# piezo-preamp-tickler_V1-01a.net
KiCad netlist of a schematic drawn in EAGLE
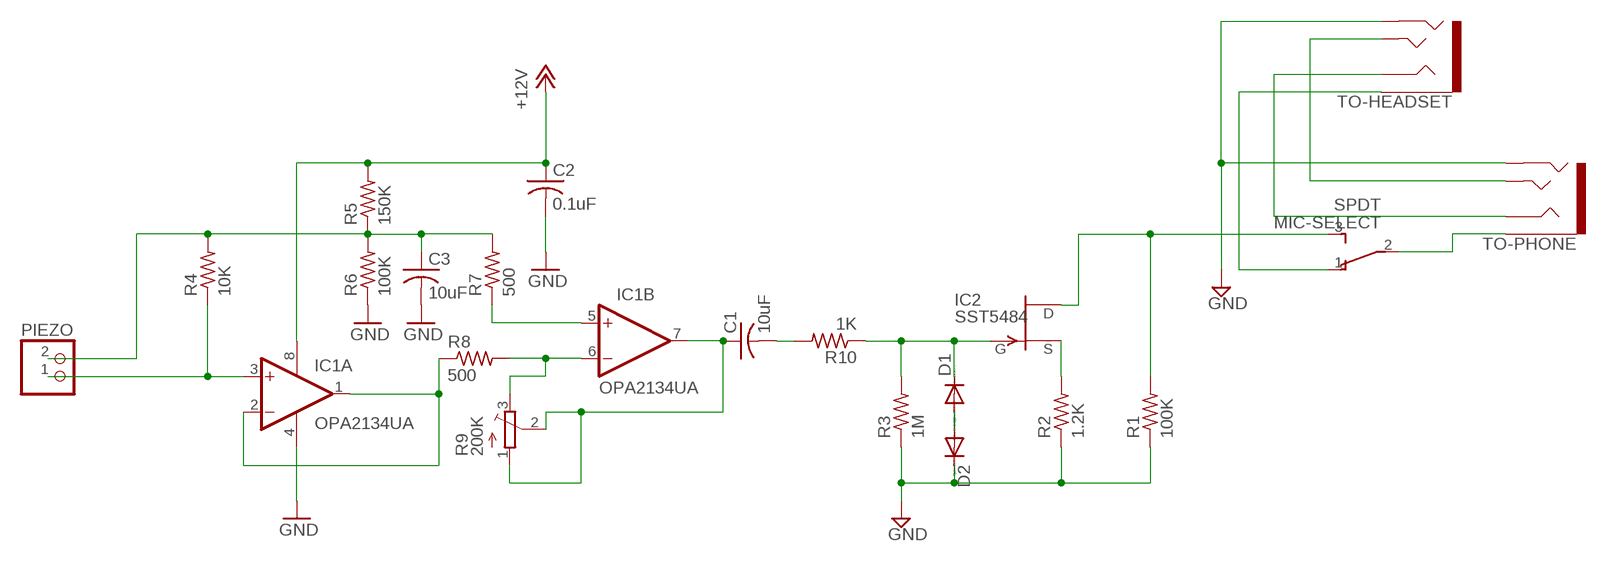
[diagram p0: schematic, sheet 1]
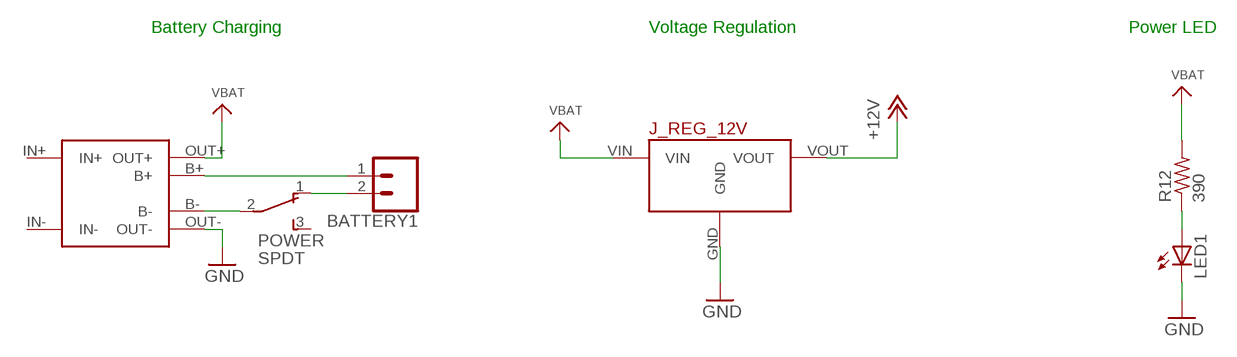
[diagram p1: schematic, sheet 2]

(export (version "E")
  (design (tool "Eeschema 10.0.6"))
  (components
    (comp (ref "C1")
      (value "10uF")
      (footprint "eagle-import:C0805K")
      (libsource (lib "eagle-import") (part "C-USC0805K"))
    )
    (comp (ref "C2")
      (value "0.1uF")
      (footprint "eagle-import:C0805K")
      (libsource (lib "eagle-import") (part "C-USC0805K"))
    )
    (comp (ref "C3")
      (value "10uF")
      (footprint "eagle-import:C0805K")
      (libsource (lib "eagle-import") (part "C-USC0805K"))
    )
    (comp (ref "D1")
      (value "DIODE-SOD123")
      (footprint "eagle-import:SOD123")
      (libsource (lib "eagle-import") (part "DIODE-SOD123"))
    )
    (comp (ref "D2")
      (value "DIODE-SOD123")
      (footprint "eagle-import:SOD123")
      (libsource (lib "eagle-import") (part "DIODE-SOD123"))
    )
    (comp (ref "IC1")
      (value "OPA2134UA")
      (footprint "eagle-import:SO08")
      (libsource (lib "eagle-import") (part "OPA2UA134"))
    )
    (comp (ref "IC2")
      (value "SST5484")
      (footprint "eagle-import:SOT23")
      (libsource (lib "eagle-import") (part "?548SST4"))
    )
    (comp (ref "MIC-SELECT")
      (value "SPDT")
      (footprint "eagle-import:SWITCH_SPDT-TE-CONNECT")
      (libsource (lib "eagle-import") (part "SWITCH_SPDTTE-CONNECT"))
    )
    (comp (ref "PIEZO")
      (value "JST_2PIN-THM")
      (footprint "eagle-import:JST-PH-2-THM")
      (libsource (lib "eagle-import") (part "JST_2PIN-THM"))
    )
    (comp (ref "R1")
      (value "100K")
      (footprint "eagle-import:R0603")
      (libsource (lib "eagle-import") (part "R-US_R0603"))
    )
    (comp (ref "R2")
      (value "1.2K")
      (footprint "eagle-import:R0603")
      (libsource (lib "eagle-import") (part "R-US_R0603"))
    )
    (comp (ref "R3")
      (value "1M")
      (footprint "eagle-import:R0603")
      (libsource (lib "eagle-import") (part "R-US_R0603"))
    )
    (comp (ref "R4")
      (value "10K")
      (footprint "eagle-import:R0603")
      (libsource (lib "eagle-import") (part "R-US_R0603"))
    )
    (comp (ref "R5")
      (value "150K")
      (footprint "eagle-import:R0603")
      (libsource (lib "eagle-import") (part "R-US_R0603"))
    )
    (comp (ref "R6")
      (value "100K")
      (footprint "eagle-import:R0603")
      (libsource (lib "eagle-import") (part "R-US_R0603"))
    )
    (comp (ref "R7")
      (value "500")
      (footprint "eagle-import:R0603")
      (libsource (lib "eagle-import") (part "R-US_R0603"))
    )
    (comp (ref "R8")
      (value "500")
      (footprint "eagle-import:R0603")
      (libsource (lib "eagle-import") (part "R-US_R0603"))
    )
    (comp (ref "R9")
      (value "200K")
      (footprint "eagle-import:TC33X")
      (libsource (lib "eagle-import") (part "TRIMPOTTC33X"))
    )
    (comp (ref "R10")
      (value "1K")
      (footprint "eagle-import:R0603")
      (libsource (lib "eagle-import") (part "R-US_R0603"))
    )
    (comp (ref "TO-HEADSET")
      (value "AUDIO-JACK3LGPADS")
      (footprint "eagle-import:AUDIO-JACK-TRRS-SMD")
      (libsource (lib "eagle-import") (part "AUDIO-JACK3LGPADS"))
    )
    (comp (ref "TO-PHONE")
      (value "AUDIO-JACK3LGPADS")
      (footprint "eagle-import:AUDIO-JACK-TRRS-SMD")
      (libsource (lib "eagle-import") (part "AUDIO-JACK3LGPADS"))
    )
    (comp (ref "BATTERY1")
      (value "CONN_02LOCK")
      (footprint "eagle-import:1X02_LOCK")
      (libsource (lib "eagle-import") (part "CONN_02LOCK"))
    )
    (comp (ref "J_REG_12V")
      (value "POLOLU_VOLTAGE_REGULATORS_3PIN")
      (footprint "eagle-import:POLOLU_5V-12V_STEPUP_U3V12F5-U3V12F12")
      (libsource (lib "eagle-import") (part "POLOLU_VOLTAGE_REGULATORS_3PIN"))
    )
    (comp (ref "LED1")
      (value "LED3MM")
      (footprint "eagle-import:LED3MM")
      (libsource (lib "eagle-import") (part "LED3MM"))
    )
    (comp (ref "POWER")
      (value "SPDT")
      (footprint "eagle-import:SWITCH_SPDT-TE-CONNECT")
      (libsource (lib "eagle-import") (part "SWITCH_SPDTTE-CONNECT"))
    )
    (comp (ref "R12")
      (value "390")
      (footprint "eagle-import:R0805")
      (libsource (lib "eagle-import") (part "R-US_R0805"))
    )
    (comp (ref "USB-LIPO-CHARGER")
      (value "TP4056-MODULE")
      (footprint "eagle-import:TP4056-LITHIUM-PROTECTED-MODULE")
      (libsource (lib "eagle-import") (part "TP4056-MODULE"))
    )
  )
  (nets
    (net (code "1") (name "+12V") (class "Default")
      (node (ref "C2") (pin "1") (pinfunction "1_1") (pintype "passive"))
      (node (ref "IC1") (pin "8") (pinfunction "V+_8") (pintype "power_in"))
      (node (ref "J_REG_12V") (pin "VOUT") (pinfunction "VOUT_VOUT") (pintype "bidirectional"))
      (node (ref "R5") (pin "2") (pinfunction "2_2") (pintype "passive"))
    )
    (net (code "2") (name "GND") (class "Default")
      (node (ref "C2") (pin "2") (pinfunction "2_2") (pintype "passive"))
      (node (ref "C3") (pin "2") (pinfunction "2_2") (pintype "passive"))
      (node (ref "D2") (pin "C") (pinfunction "C_C") (pintype "passive"))
      (node (ref "IC1") (pin "4") (pinfunction "V-_4") (pintype "power_in"))
      (node (ref "J_REG_12V") (pin "GND") (pinfunction "GND_GND") (pintype "bidirectional"))
      (node (ref "LED1") (pin "K") (pinfunction "C_K") (pintype "passive"))
      (node (ref "R1") (pin "1") (pinfunction "1_1") (pintype "passive"))
      (node (ref "R2") (pin "1") (pinfunction "1_1") (pintype "passive"))
      (node (ref "R3") (pin "1") (pinfunction "1_1") (pintype "passive"))
      (node (ref "R6") (pin "1") (pinfunction "1_1") (pintype "passive"))
      (node (ref "TO-HEADSET") (pin "RING2") (pinfunction "RING2_RING2") (pintype "bidirectional"))
      (node (ref "TO-PHONE") (pin "RING2") (pinfunction "RING2_RING2") (pintype "bidirectional"))
      (node (ref "USB-LIPO-CHARGER") (pin "OUT-") (pinfunction "OUT-_OUT-") (pintype "power_in"))
    )
    (net (code "3") (name "IN+") (class "Default")
      (node (ref "USB-LIPO-CHARGER") (pin "IN+") (pinfunction "IN+_IN+") (pintype "power_in"))
    )
    (net (code "4") (name "IN-") (class "Default")
      (node (ref "USB-LIPO-CHARGER") (pin "IN-") (pinfunction "IN-_IN-") (pintype "power_in"))
    )
    (net (code "5") (name "Net-(BATTERY1-Pad1)") (class "Default")
      (node (ref "BATTERY1") (pin "1") (pinfunction "1_1") (pintype "passive"))
      (node (ref "USB-LIPO-CHARGER") (pin "B+") (pinfunction "B+_B+") (pintype "power_in"))
    )
    (net (code "6") (name "Net-(BATTERY1-Pad2)") (class "Default")
      (node (ref "BATTERY1") (pin "2") (pinfunction "2_2") (pintype "passive"))
      (node (ref "POWER") (pin "1") (pinfunction "1_1") (pintype "passive"))
    )
    (net (code "7") (name "Net-(C1-Pad2)") (class "Default")
      (node (ref "C1") (pin "2") (pinfunction "2_2") (pintype "passive"))
      (node (ref "R10") (pin "2") (pinfunction "2_2") (pintype "passive"))
    )
    (net (code "8") (name "Net-(D1-PadA)") (class "Default")
      (node (ref "D1") (pin "A") (pinfunction "A_A") (pintype "passive"))
      (node (ref "D2") (pin "A") (pinfunction "A_A") (pintype "passive"))
    )
    (net (code "9") (name "Net-(IC1A-+IN)") (class "Default")
      (node (ref "IC1") (pin "3") (pinfunction "+IN_3") (pintype "input"))
      (node (ref "PIEZO") (pin "1") (pinfunction "2_1") (pintype "passive"))
      (node (ref "R4") (pin "1") (pinfunction "1_1") (pintype "passive"))
    )
    (net (code "10") (name "Net-(IC1A--IN)") (class "Default")
      (node (ref "IC1") (pin "1") (pinfunction "OUT_1") (pintype "output"))
      (node (ref "IC1") (pin "2") (pinfunction "-IN_2") (pintype "input"))
      (node (ref "R8") (pin "1") (pinfunction "1_1") (pintype "passive"))
    )
    (net (code "11") (name "Net-(IC1B-+IN)") (class "Default")
      (node (ref "IC1") (pin "5") (pinfunction "+IN_5") (pintype "input"))
      (node (ref "R7") (pin "1") (pinfunction "1_1") (pintype "passive"))
    )
    (net (code "12") (name "Net-(IC1B--IN)") (class "Default")
      (node (ref "IC1") (pin "6") (pinfunction "-IN_6") (pintype "input"))
      (node (ref "R8") (pin "2") (pinfunction "2_2") (pintype "passive"))
      (node (ref "R9") (pin "3") (pinfunction "E_3") (pintype "passive"))
    )
    (net (code "13") (name "Net-(IC1B-OUT)") (class "Default")
      (node (ref "C1") (pin "1") (pinfunction "1_1") (pintype "passive"))
      (node (ref "IC1") (pin "7") (pinfunction "OUT_7") (pintype "output"))
      (node (ref "R9") (pin "1") (pinfunction "A_1") (pintype "passive"))
      (node (ref "R9") (pin "2") (pinfunction "S_2") (pintype "passive"))
    )
    (net (code "14") (name "Net-(IC2-D)") (class "Default")
      (node (ref "IC2") (pin "1") (pinfunction "D_1") (pintype "passive"))
      (node (ref "MIC-SELECT") (pin "3") (pinfunction "3_3") (pintype "passive"))
      (node (ref "R1") (pin "2") (pinfunction "2_2") (pintype "passive"))
    )
    (net (code "15") (name "Net-(IC2-G)") (class "Default")
      (node (ref "D1") (pin "C") (pinfunction "C_C") (pintype "passive"))
      (node (ref "IC2") (pin "3") (pinfunction "G_3") (pintype "passive"))
      (node (ref "R10") (pin "1") (pinfunction "1_1") (pintype "passive"))
      (node (ref "R3") (pin "2") (pinfunction "2_2") (pintype "passive"))
    )
    (net (code "16") (name "Net-(IC2-S)") (class "Default")
      (node (ref "IC2") (pin "2") (pinfunction "S_2") (pintype "passive"))
      (node (ref "R2") (pin "2") (pinfunction "2_2") (pintype "passive"))
    )
    (net (code "17") (name "Net-(LED1-PadA)") (class "Default")
      (node (ref "LED1") (pin "A") (pinfunction "A_A") (pintype "passive"))
      (node (ref "R12") (pin "1") (pinfunction "1_1") (pintype "passive"))
    )
    (net (code "18") (name "Net-(MIC-SELECT-Pad1)") (class "Default")
      (node (ref "MIC-SELECT") (pin "1") (pinfunction "1_1") (pintype "passive"))
      (node (ref "TO-HEADSET") (pin "EARTH") (pinfunction "EARTH_EARTH") (pintype "bidirectional"))
    )
    (net (code "19") (name "Net-(MIC-SELECT-Pad2)") (class "Default")
      (node (ref "MIC-SELECT") (pin "2") (pinfunction "2_2") (pintype "passive"))
      (node (ref "TO-PHONE") (pin "EARTH") (pinfunction "EARTH_EARTH") (pintype "bidirectional"))
    )
    (net (code "20") (name "Net-(PIEZO-1)") (class "Default")
      (node (ref "C3") (pin "1") (pinfunction "1_1") (pintype "passive"))
      (node (ref "PIEZO") (pin "2") (pinfunction "1_2") (pintype "passive"))
      (node (ref "R4") (pin "2") (pinfunction "2_2") (pintype "passive"))
      (node (ref "R5") (pin "1") (pinfunction "1_1") (pintype "passive"))
      (node (ref "R6") (pin "2") (pinfunction "2_2") (pintype "passive"))
      (node (ref "R7") (pin "2") (pinfunction "2_2") (pintype "passive"))
    )
    (net (code "21") (name "Net-(POWER-Pad2)") (class "Default")
      (node (ref "POWER") (pin "2") (pinfunction "2_2") (pintype "passive"))
      (node (ref "USB-LIPO-CHARGER") (pin "B-") (pinfunction "B-_B-") (pintype "power_in"))
    )
    (net (code "22") (name "Net-(TO-HEADSET-PadRING1)") (class "Default")
      (node (ref "TO-HEADSET") (pin "RING1") (pinfunction "RING1_RING1") (pintype "bidirectional"))
      (node (ref "TO-PHONE") (pin "RING1") (pinfunction "RING1_RING1") (pintype "bidirectional"))
    )
    (net (code "23") (name "Net-(TO-HEADSET-PadTIP)") (class "Default")
      (node (ref "TO-HEADSET") (pin "TIP") (pinfunction "TIP_TIP") (pintype "bidirectional"))
      (node (ref "TO-PHONE") (pin "TIP") (pinfunction "TIP_TIP") (pintype "bidirectional"))
    )
    (net (code "24") (name "VBAT") (class "Default")
      (node (ref "J_REG_12V") (pin "VIN") (pinfunction "VIN_VIN") (pintype "bidirectional"))
      (node (ref "R12") (pin "2") (pinfunction "2_2") (pintype "passive"))
      (node (ref "USB-LIPO-CHARGER") (pin "OUT+") (pinfunction "OUT+_OUT+") (pintype "power_in"))
    )
    (net (code "25") (name "unconnected-(POWER-Pad3)") (class "Default")
      (node (ref "POWER") (pin "3") (pinfunction "3_3") (pintype "passive"))
    )
  )
)
